# 3_-BLE.net
KiCad netlist of a schematic drawn in Altium Designer
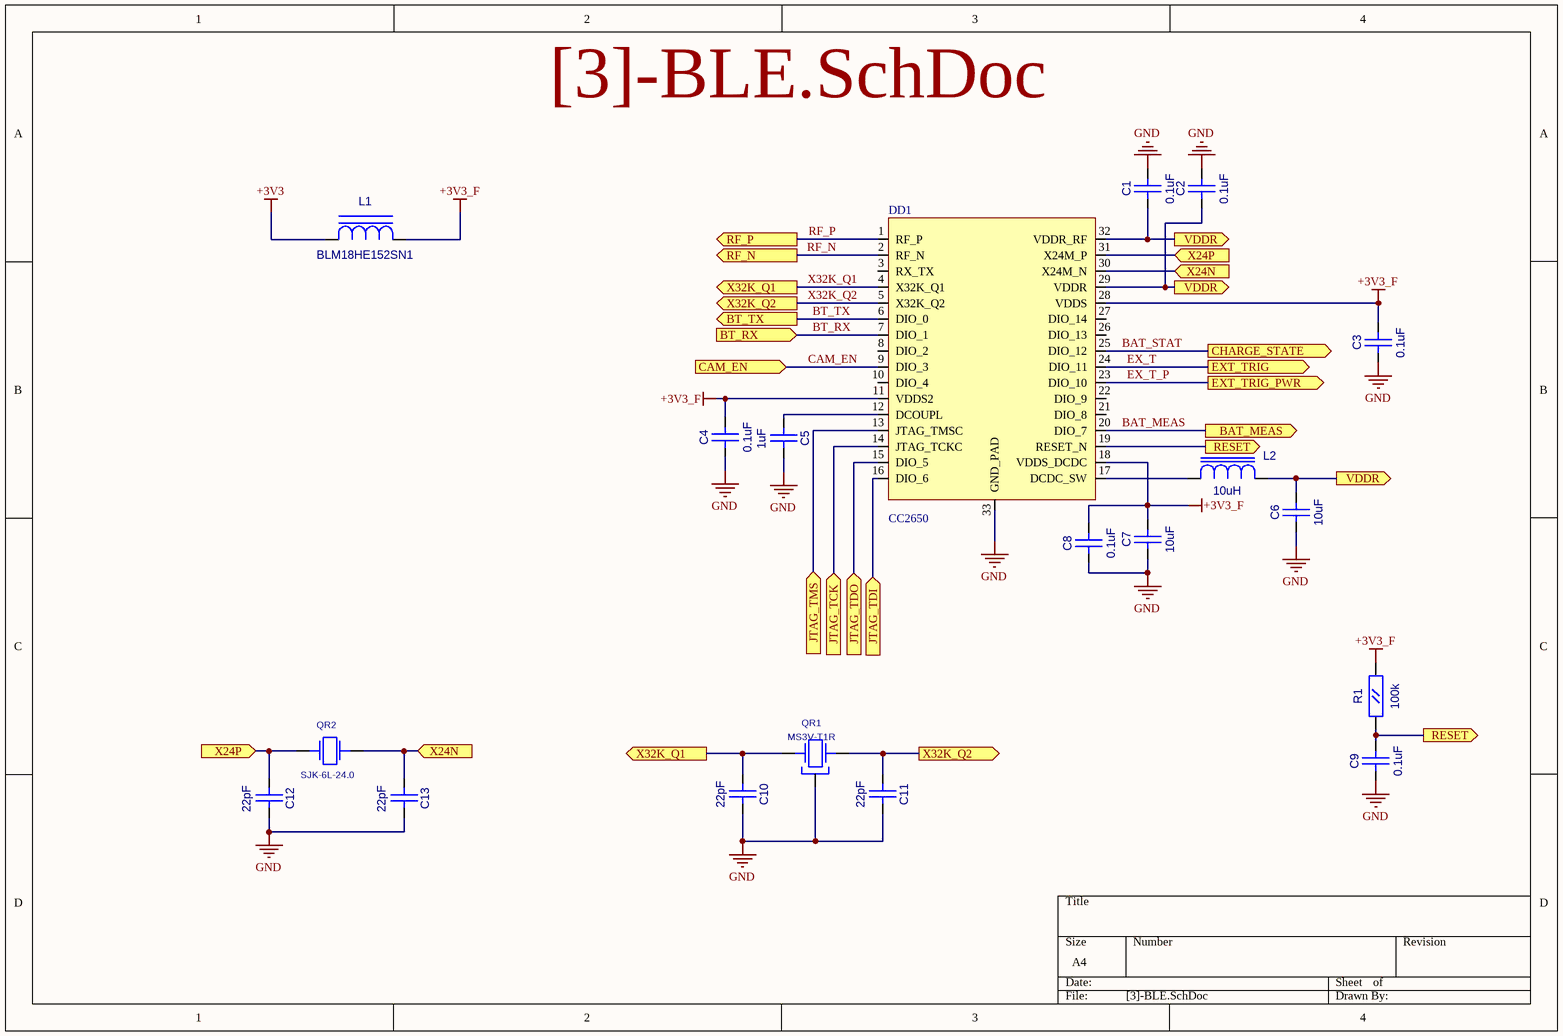
[diagram p0: [3]-BLE.SchDoc]

(export (version "E")
  (design (tool "Eeschema 10.0.6"))
  (components
    (comp (ref "C1")
      (value "0.1uF")
      (footprint "CC0603")
      (description "CC0603")
      (libsource (lib "gprs_modem_2") (part "CC0603"))
    )
    (comp (ref "C2")
      (value "0.1uF")
      (footprint "CC0603")
      (description "CC0603")
      (libsource (lib "gprs_modem_2") (part "CC0603"))
    )
    (comp (ref "C3")
      (value "0.1uF")
      (footprint "CC0603")
      (description "CC0603")
      (libsource (lib "gprs_modem_2") (part "CC0603"))
    )
    (comp (ref "C4")
      (value "0.1uF")
      (footprint "CC0603")
      (description "CC0603")
      (libsource (lib "gprs_modem_2") (part "CC0603"))
    )
    (comp (ref "C5")
      (value "1uF")
      (footprint "CC0603")
      (description "CC0603")
      (libsource (lib "gprs_modem_2") (part "CC0603"))
    )
    (comp (ref "C6")
      (value "10uF")
      (footprint "CC0805")
      (description "CC0805")
      (libsource (lib "gprs_modem_2") (part "CC0805"))
    )
    (comp (ref "C7")
      (value "10uF")
      (footprint "CC0805")
      (description "CC0805")
      (libsource (lib "gprs_modem_2") (part "CC0805"))
    )
    (comp (ref "C8")
      (value "0.1uF")
      (footprint "CC0603")
      (description "CC0603")
      (libsource (lib "gprs_modem_2") (part "CC0603"))
    )
    (comp (ref "C9")
      (value "0.1uF")
      (footprint "CC0603")
      (description "CC0603")
      (libsource (lib "gprs_modem_2") (part "CC0603"))
    )
    (comp (ref "C10")
      (value "22pF")
      (footprint "CC0603")
      (description "CC0603")
      (libsource (lib "gprs_modem_2") (part "CC0603"))
    )
    (comp (ref "C11")
      (value "22pF")
      (footprint "CC0603")
      (description "CC0603")
      (libsource (lib "gprs_modem_2") (part "CC0603"))
    )
    (comp (ref "C12")
      (value "22pF")
      (footprint "CC0603")
      (description "CC0603")
      (libsource (lib "gprs_modem_2") (part "CC0603"))
    )
    (comp (ref "C13")
      (value "22pF")
      (footprint "CC0603")
      (description "CC0603")
      (libsource (lib "gprs_modem_2") (part "CC0603"))
    )
    (comp (ref "DD1")
      (value "CC2650")
      (footprint "QFN32_TI")
      (description "CC2650RHBT")
      (libsource (lib "gprs_modem_2") (part "CC2650RHB"))
    )
    (comp (ref "L1")
      (value "BLM18HE152SN1")
      (footprint "L0603")
      (description "L0603")
      (libsource (lib "gprs_modem_2") (part "L0603"))
    )
    (comp (ref "L2")
      (value "10uH")
      (footprint "RC0805")
      (description "L0805")
      (libsource (lib "gprs_modem_2") (part "L0805"))
    )
    (comp (ref "QR1")
      (value "MS3V-T1R")
      (footprint "MS3V-T1R")
      (description "CRYSTAL_32768 Hz")
      (libsource (lib "gprs_modem_2") (part "MS3V-T1R"))
    )
    (comp (ref "QR2")
      (value "SJK-6L-24.0")
      (footprint "AC5032_2")
      (description "AC5032/2")
      (libsource (lib "gprs_modem_2") (part "AC5032_2"))
    )
    (comp (ref "R1")
      (value "100k")
      (footprint "RC0603")
      (description "RC0603")
      (libsource (lib "gprs_modem_2") (part "RC0603"))
    )
  )
  (nets
    (net (code "1") (name "+3V3") (class "Default")
      (node (ref "L1") (pin "1") (pinfunction "A_1") (pintype "passive"))
    )
    (net (code "2") (name "+3V3_F") (class "Default")
      (node (ref "C3") (pin "2") (pinfunction "B_2") (pintype "passive"))
      (node (ref "C4") (pin "2") (pinfunction "B_2") (pintype "passive"))
      (node (ref "C7") (pin "2") (pinfunction "B_2") (pintype "passive"))
      (node (ref "C8") (pin "2") (pinfunction "B_2") (pintype "passive"))
      (node (ref "DD1") (pin "11") (pinfunction "VDDS2_11") (pintype "passive"))
      (node (ref "DD1") (pin "18") (pinfunction "VDDS_DCDC_18") (pintype "passive"))
      (node (ref "DD1") (pin "28") (pinfunction "VDDS_28") (pintype "passive"))
      (node (ref "L1") (pin "2") (pinfunction "C_2") (pintype "passive"))
      (node (ref "R1") (pin "2") (pinfunction "B_2") (pintype "passive"))
    )
    (net (code "3") (name "/BAT_MEAS") (class "Default")
      (node (ref "DD1") (pin "20") (pinfunction "DIO_7_20") (pintype "passive"))
    )
    (net (code "4") (name "/BAT_STAT") (class "Default")
      (node (ref "DD1") (pin "25") (pinfunction "DIO_12_25") (pintype "passive"))
    )
    (net (code "5") (name "/BT_RX") (class "Default")
      (node (ref "DD1") (pin "7") (pinfunction "DIO_1_7") (pintype "passive"))
    )
    (net (code "6") (name "/BT_TX") (class "Default")
      (node (ref "DD1") (pin "6") (pinfunction "DIO_0_6") (pintype "passive"))
    )
    (net (code "7") (name "/CAM_EN") (class "Default")
      (node (ref "DD1") (pin "9") (pinfunction "DIO_3_9") (pintype "passive"))
    )
    (net (code "8") (name "/EX_T") (class "Default")
      (node (ref "DD1") (pin "24") (pinfunction "DIO_11_24") (pintype "passive"))
    )
    (net (code "9") (name "/EX_T_P") (class "Default")
      (node (ref "DD1") (pin "23") (pinfunction "DIO_10_23") (pintype "passive"))
    )
    (net (code "10") (name "/JTAG_TCK") (class "Default")
      (node (ref "DD1") (pin "14") (pinfunction "JTAG_TCKC_14") (pintype "passive"))
    )
    (net (code "11") (name "/JTAG_TDI") (class "Default")
      (node (ref "DD1") (pin "16") (pinfunction "DIO_6_16") (pintype "passive"))
    )
    (net (code "12") (name "/JTAG_TDO") (class "Default")
      (node (ref "DD1") (pin "15") (pinfunction "DIO_5_15") (pintype "passive"))
    )
    (net (code "13") (name "/JTAG_TMS") (class "Default")
      (node (ref "DD1") (pin "13") (pinfunction "JTAG_TMSC_13") (pintype "passive"))
    )
    (net (code "14") (name "/RESET") (class "Default")
      (node (ref "C9") (pin "2") (pinfunction "B_2") (pintype "passive"))
      (node (ref "DD1") (pin "19") (pinfunction "RESET_N_19") (pintype "passive"))
      (node (ref "R1") (pin "1") (pinfunction "A_1") (pintype "passive"))
    )
    (net (code "15") (name "/RF_N") (class "Default")
      (node (ref "DD1") (pin "2") (pinfunction "RF_N_2") (pintype "passive"))
    )
    (net (code "16") (name "/RF_P") (class "Default")
      (node (ref "DD1") (pin "1") (pinfunction "RF_P_1") (pintype "passive"))
    )
    (net (code "17") (name "/VDDR") (class "Default")
      (node (ref "C1") (pin "1") (pinfunction "A_1") (pintype "passive"))
      (node (ref "C2") (pin "1") (pinfunction "A_1") (pintype "passive"))
      (node (ref "C6") (pin "2") (pinfunction "B_2") (pintype "passive"))
      (node (ref "DD1") (pin "29") (pinfunction "VDDR_29") (pintype "passive"))
      (node (ref "DD1") (pin "32") (pinfunction "VDDR_RF_32") (pintype "passive"))
      (node (ref "L2") (pin "2") (pinfunction "B_2") (pintype "passive"))
    )
    (net (code "18") (name "/X24N") (class "Default")
      (node (ref "C13") (pin "1") (pinfunction "A_1") (pintype "passive"))
      (node (ref "DD1") (pin "30") (pinfunction "X24M_N_30") (pintype "passive"))
      (node (ref "QR2") (pin "2") (pintype "passive"))
    )
    (net (code "19") (name "/X24P") (class "Default")
      (node (ref "C12") (pin "1") (pinfunction "A_1") (pintype "passive"))
      (node (ref "DD1") (pin "31") (pinfunction "X24M_P_31") (pintype "passive"))
      (node (ref "QR2") (pin "1") (pintype "passive"))
    )
    (net (code "20") (name "/X32K_Q1") (class "Default")
      (node (ref "C10") (pin "1") (pinfunction "A_1") (pintype "passive"))
      (node (ref "DD1") (pin "4") (pinfunction "X32K_Q1_4") (pintype "passive"))
      (node (ref "QR1") (pin "2") (pinfunction "X2_2") (pintype "passive"))
    )
    (net (code "21") (name "/X32K_Q2") (class "Default")
      (node (ref "C11") (pin "1") (pinfunction "A_1") (pintype "passive"))
      (node (ref "DD1") (pin "5") (pinfunction "X32K_Q2_5") (pintype "passive"))
      (node (ref "QR1") (pin "1") (pinfunction "X1_1") (pintype "passive"))
    )
    (net (code "22") (name "GND") (class "Default")
      (node (ref "C1") (pin "2") (pinfunction "B_2") (pintype "passive"))
      (node (ref "C10") (pin "2") (pinfunction "B_2") (pintype "passive"))
      (node (ref "C11") (pin "2") (pinfunction "B_2") (pintype "passive"))
      (node (ref "C12") (pin "2") (pinfunction "B_2") (pintype "passive"))
      (node (ref "C13") (pin "2") (pinfunction "B_2") (pintype "passive"))
      (node (ref "C2") (pin "2") (pinfunction "B_2") (pintype "passive"))
      (node (ref "C3") (pin "1") (pinfunction "A_1") (pintype "passive"))
      (node (ref "C4") (pin "1") (pinfunction "A_1") (pintype "passive"))
      (node (ref "C5") (pin "2") (pinfunction "B_2") (pintype "passive"))
      (node (ref "C6") (pin "1") (pinfunction "A_1") (pintype "passive"))
      (node (ref "C7") (pin "1") (pinfunction "A_1") (pintype "passive"))
      (node (ref "C8") (pin "1") (pinfunction "A_1") (pintype "passive"))
      (node (ref "C9") (pin "1") (pinfunction "A_1") (pintype "passive"))
      (node (ref "DD1") (pin "33") (pinfunction "GND_PAD_33") (pintype "passive"))
      (node (ref "QR1") (pin "3") (pinfunction "3_3") (pintype "passive"))
    )
    (net (code "23") (name "Net-(C5-A)") (class "Default")
      (node (ref "C5") (pin "1") (pinfunction "A_1") (pintype "passive"))
      (node (ref "DD1") (pin "12") (pinfunction "DCOUPL_12") (pintype "passive"))
    )
    (net (code "24") (name "Net-(DD1-DCDC_SW)") (class "Default")
      (node (ref "DD1") (pin "17") (pinfunction "DCDC_SW_17") (pintype "passive"))
      (node (ref "L2") (pin "1") (pinfunction "A_1") (pintype "passive"))
    )
    (net (code "25") (name "unconnected-(DD1-DIO_2-Pad8)") (class "Default")
      (node (ref "DD1") (pin "8") (pinfunction "DIO_2_8") (pintype "passive"))
    )
    (net (code "26") (name "unconnected-(DD1-DIO_4-Pad10)") (class "Default")
      (node (ref "DD1") (pin "10") (pinfunction "DIO_4_10") (pintype "passive"))
    )
    (net (code "27") (name "unconnected-(DD1-DIO_8-Pad21)") (class "Default")
      (node (ref "DD1") (pin "21") (pinfunction "DIO_8_21") (pintype "passive"))
    )
    (net (code "28") (name "unconnected-(DD1-DIO_9-Pad22)") (class "Default")
      (node (ref "DD1") (pin "22") (pinfunction "DIO_9_22") (pintype "passive"))
    )
    (net (code "29") (name "unconnected-(DD1-DIO_13-Pad26)") (class "Default")
      (node (ref "DD1") (pin "26") (pinfunction "DIO_13_26") (pintype "passive"))
    )
    (net (code "30") (name "unconnected-(DD1-DIO_14-Pad27)") (class "Default")
      (node (ref "DD1") (pin "27") (pinfunction "DIO_14_27") (pintype "passive"))
    )
    (net (code "31") (name "unconnected-(DD1-RX_TX-Pad3)") (class "Default")
      (node (ref "DD1") (pin "3") (pinfunction "RX_TX_3") (pintype "passive"))
    )
  )
)
